# PWM.net
KiCad netlist of a schematic drawn in EAGLE
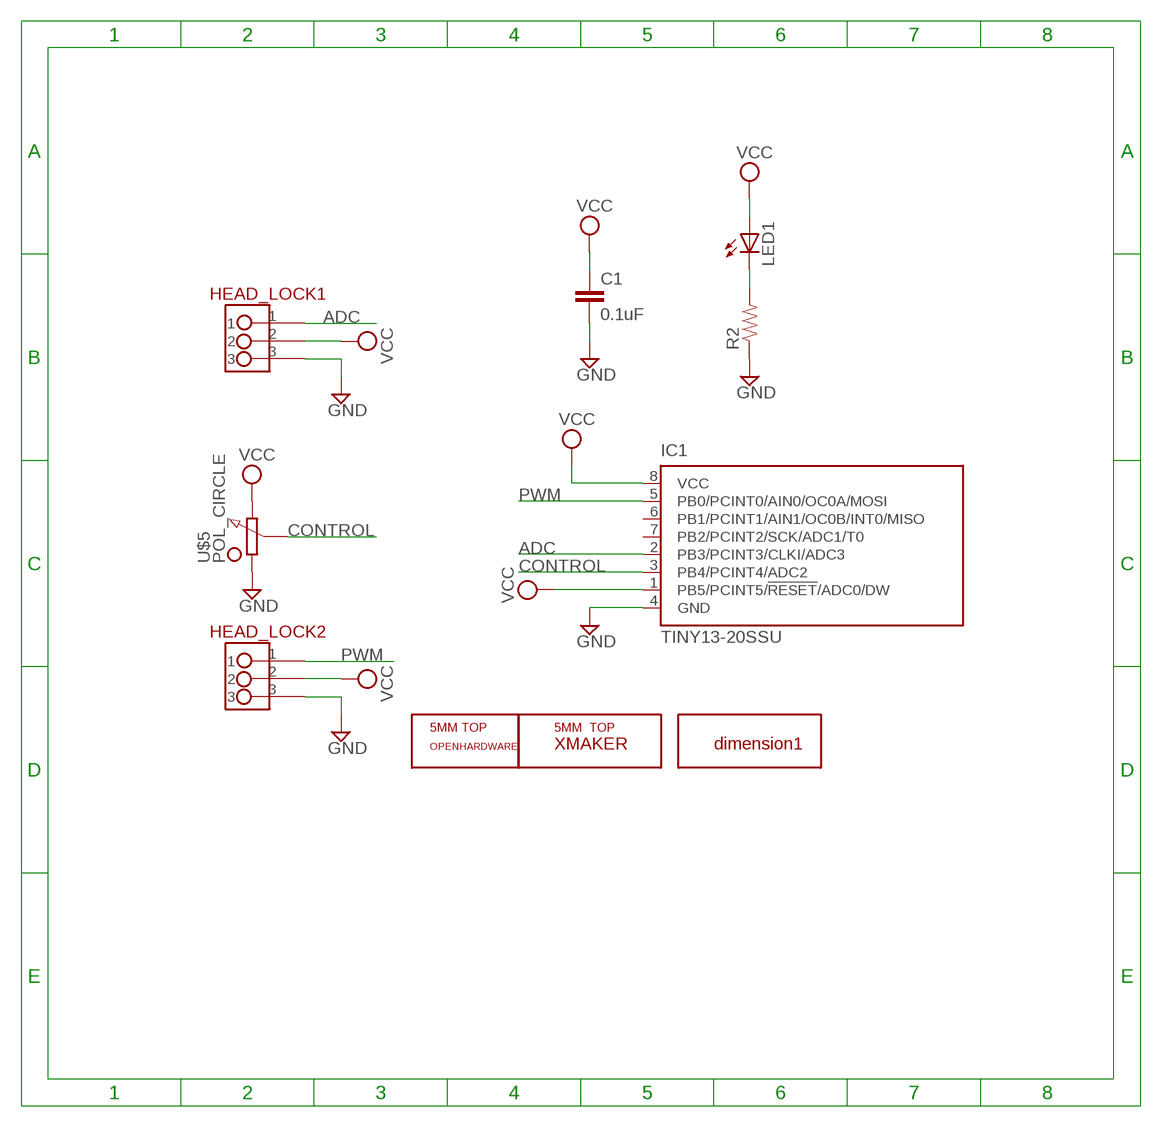
[diagram p0: schematic, sheet 1]

(export (version "E")
  (design (tool "Eeschema 10.0.6"))
  (components
    (comp (ref "C1")
      (value "0.1uF")
      (footprint "eagle-import:0603-CAP")
      (libsource (lib "eagle-import") (part "CAP0603-CAP"))
    )
    (comp (ref "HEAD_LOCK1")
      (value "HEAD_LOCK")
      (footprint "eagle-import:HEAD_LOCK")
      (libsource (lib "eagle-import") (part "HEAD_LOCK"))
    )
    (comp (ref "HEAD_LOCK2")
      (value "HEAD_LOCK")
      (footprint "eagle-import:HEAD_LOCK")
      (libsource (lib "eagle-import") (part "HEAD_LOCK"))
    )
    (comp (ref "IC1")
      (value "TINY13-20SSU")
      (footprint "eagle-import:8S1")
      (fields (field (name "MPN") "ATTINY13-20SSU"))
      (libsource (lib "eagle-import") (part "TINY13SSU-20"))
    )
    (comp (ref "LED1")
      (value "LED_ESML0603")
      (footprint "eagle-import:LED_SML0603")
      (libsource (lib "eagle-import") (part "LED_ESML0603"))
    )
    (comp (ref "R2")
      (value "0.27OHM-1/10W-1%(0603)")
      (footprint "eagle-import:0603-RES")
      (libsource (lib "eagle-import") (part "0.27OHM-1/10W-1%(0603)"))
    )
    (comp (ref "U$2")
      (value "XMAKERLOGO_5MM_TOP")
      (footprint "eagle-import:XMAKERLOGO_5MM_TOP")
      (libsource (lib "eagle-import") (part "XMAKERLOGO_5MM_TOP"))
    )
    (comp (ref "U$3")
      (value "DIMENSION1")
      (footprint "eagle-import:DIMENSION1")
      (libsource (lib "eagle-import") (part "DIMENSION1"))
    )
    (comp (ref "U$4")
      (value "OPENHARDWARE_5MM_TOP")
      (footprint "eagle-import:OPENSOURCE_5MM_TOP")
      (libsource (lib "eagle-import") (part "OPENHARDWARE_5MM_TOP"))
    )
    (comp (ref "U$5")
      (value "POL_CIRCLE")
      (footprint "eagle-import:POT_CIRCLE")
      (libsource (lib "eagle-import") (part "POL_CIRCLE"))
    )
  )
  (nets
    (net (code "1") (name "/ADC") (class "Default")
      (node (ref "HEAD_LOCK1") (pin "1") (pinfunction "1_1") (pintype "passive"))
      (node (ref "IC1") (pin "2") (pinfunction "PB3/PCINT3/CLKI/ADC3_2") (pintype "bidirectional"))
    )
    (net (code "2") (name "/CONTROL") (class "Default")
      (node (ref "IC1") (pin "3") (pinfunction "PB4/PCINT4/ADC2_3") (pintype "bidirectional"))
      (node (ref "U$5") (pin "P$2") (pinfunction "2_P$2") (pintype "passive"))
    )
    (net (code "3") (name "/PWM") (class "Default")
      (node (ref "HEAD_LOCK2") (pin "1") (pinfunction "1_1") (pintype "passive"))
      (node (ref "IC1") (pin "5") (pinfunction "PB0/PCINT0/AIN0/OC0A/MOSI_5") (pintype "bidirectional"))
    )
    (net (code "4") (name "GND") (class "Default")
      (node (ref "C1") (pin "2") (pinfunction "2_2") (pintype "passive"))
      (node (ref "HEAD_LOCK1") (pin "3") (pinfunction "3_3") (pintype "passive"))
      (node (ref "HEAD_LOCK2") (pin "3") (pinfunction "3_3") (pintype "passive"))
      (node (ref "IC1") (pin "4") (pinfunction "GND_4") (pintype "power_in"))
      (node (ref "R2") (pin "1") (pinfunction "1_1") (pintype "passive"))
      (node (ref "U$5") (pin "P$3") (pinfunction "3_P$3") (pintype "passive"))
    )
    (net (code "5") (name "Net-(LED1-PadC)") (class "Default")
      (node (ref "LED1") (pin "C") (pinfunction "C_C") (pintype "passive"))
      (node (ref "R2") (pin "2") (pinfunction "2_2") (pintype "passive"))
    )
    (net (code "6") (name "VCC") (class "Default")
      (node (ref "C1") (pin "1") (pinfunction "1_1") (pintype "passive"))
      (node (ref "HEAD_LOCK1") (pin "2") (pinfunction "2_2") (pintype "passive"))
      (node (ref "HEAD_LOCK2") (pin "2") (pinfunction "2_2") (pintype "passive"))
      (node (ref "IC1") (pin "1") (pinfunction "PB5/PCINT5/~{RESET}/ADC0/DW_1") (pintype "bidirectional"))
      (node (ref "IC1") (pin "8") (pinfunction "VCC_8") (pintype "power_in"))
      (node (ref "LED1") (pin "A") (pinfunction "A_A") (pintype "passive"))
      (node (ref "U$5") (pin "P$1") (pinfunction "1_P$1") (pintype "passive"))
    )
    (net (code "7") (name "unconnected-(IC1-PB1{slash}PCINT1{slash}AIN1{slash}OC0B{slash}INT0{slash}MISO-Pad6)") (class "Default")
      (node (ref "IC1") (pin "6") (pinfunction "PB1/PCINT1/AIN1/OC0B/INT0/MISO_6") (pintype "bidirectional"))
    )
    (net (code "8") (name "unconnected-(IC1-PB2{slash}PCINT2{slash}SCK{slash}ADC1{slash}T0-Pad7)") (class "Default")
      (node (ref "IC1") (pin "7") (pinfunction "PB2/PCINT2/SCK/ADC1/T0_7") (pintype "bidirectional"))
    )
  )
)
